# FloatWatch-One.net
KiCad netlist of a schematic drawn in EAGLE
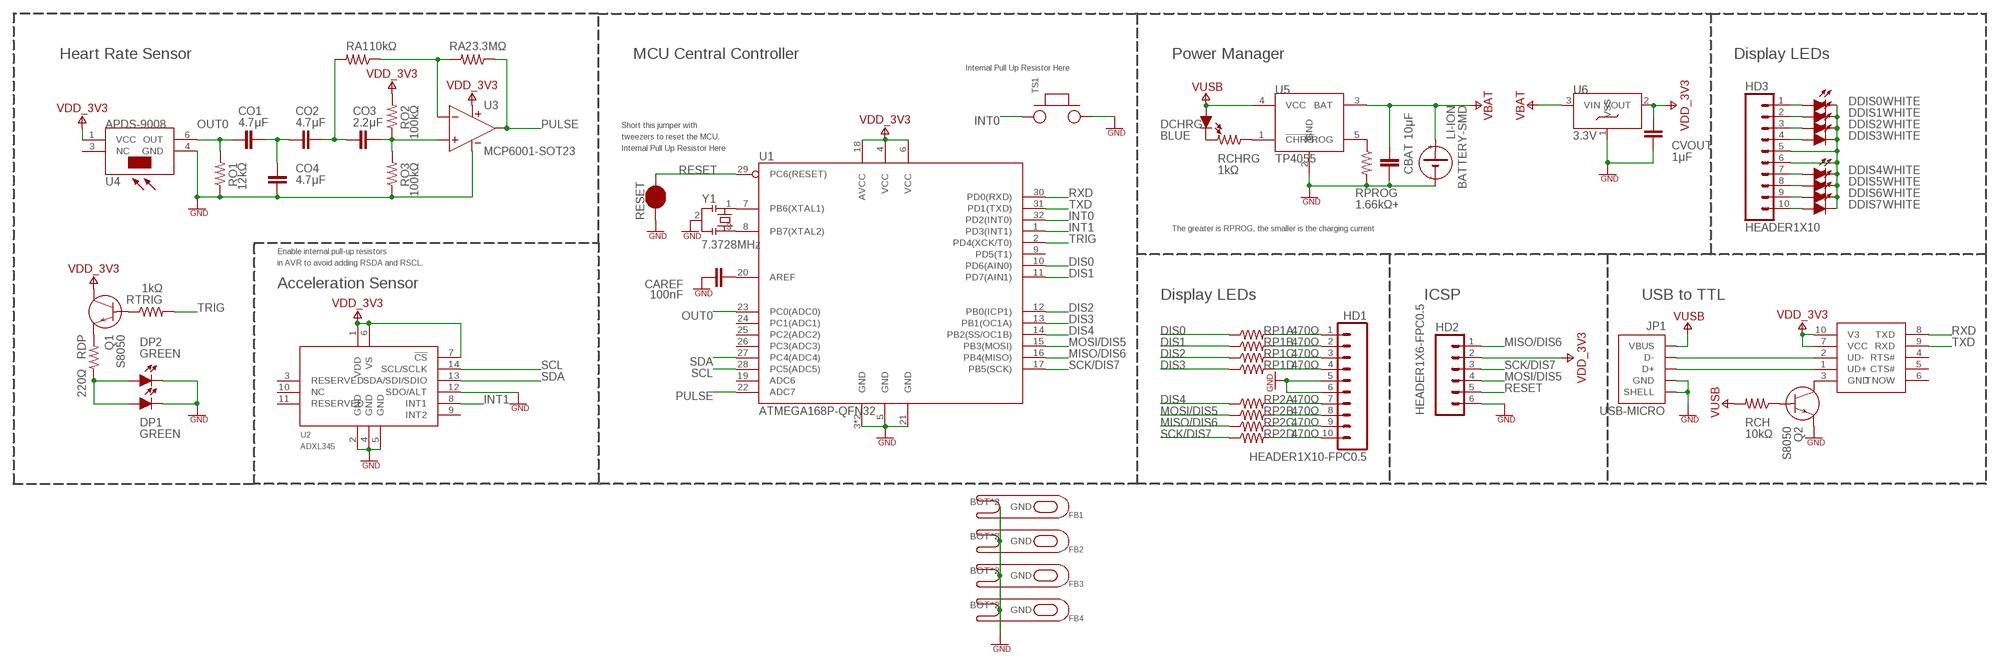
[diagram p0: schematic, sheet 1]

(export (version "E")
  (design (tool "Eeschema 10.0.6"))
  (components
    (comp (ref "CAREF")
      (value "100nF")
      (footprint "eagle-import:SMD0603")
      (libsource (lib "eagle-import") (part "CAP-0603"))
    )
    (comp (ref "CBAT")
      (value "10μF")
      (footprint "eagle-import:SMD0603")
      (libsource (lib "eagle-import") (part "CAP-0603"))
    )
    (comp (ref "CO1")
      (value "4.7μF")
      (footprint "eagle-import:SMD0603")
      (libsource (lib "eagle-import") (part "CAP-0603"))
    )
    (comp (ref "CO2")
      (value "4.7μF")
      (footprint "eagle-import:SMD0603")
      (libsource (lib "eagle-import") (part "CAP-0603"))
    )
    (comp (ref "CO3")
      (value "2.2μF")
      (footprint "eagle-import:SMD0603")
      (libsource (lib "eagle-import") (part "CAP-0603"))
    )
    (comp (ref "CO4")
      (value "4.7μF")
      (footprint "eagle-import:SMD0603")
      (libsource (lib "eagle-import") (part "CAP-0603"))
    )
    (comp (ref "CVOUT")
      (value "1μF")
      (footprint "eagle-import:SMD0603")
      (libsource (lib "eagle-import") (part "CAP-0603"))
    )
    (comp (ref "DCHRG")
      (value "BLUE")
      (footprint "eagle-import:LED-0603")
      (libsource (lib "eagle-import") (part "LED-0603"))
    )
    (comp (ref "DDIS0")
      (value "WHITE")
      (footprint "eagle-import:LED-0603")
      (libsource (lib "eagle-import") (part "LED-0603"))
    )
    (comp (ref "DDIS1")
      (value "WHITE")
      (footprint "eagle-import:LED-0603")
      (libsource (lib "eagle-import") (part "LED-0603"))
    )
    (comp (ref "DDIS2")
      (value "WHITE")
      (footprint "eagle-import:LED-0603")
      (libsource (lib "eagle-import") (part "LED-0603"))
    )
    (comp (ref "DDIS3")
      (value "WHITE")
      (footprint "eagle-import:LED-0603")
      (libsource (lib "eagle-import") (part "LED-0603"))
    )
    (comp (ref "DDIS4")
      (value "WHITE")
      (footprint "eagle-import:LED-0603")
      (libsource (lib "eagle-import") (part "LED-0603"))
    )
    (comp (ref "DDIS5")
      (value "WHITE")
      (footprint "eagle-import:LED-0603")
      (libsource (lib "eagle-import") (part "LED-0603"))
    )
    (comp (ref "DDIS6")
      (value "WHITE")
      (footprint "eagle-import:LED-0603")
      (libsource (lib "eagle-import") (part "LED-0603"))
    )
    (comp (ref "DDIS7")
      (value "WHITE")
      (footprint "eagle-import:LED-0603")
      (libsource (lib "eagle-import") (part "LED-0603"))
    )
    (comp (ref "DP1")
      (value "GREEN")
      (footprint "eagle-import:LED-1206")
      (libsource (lib "eagle-import") (part "LED-1206"))
    )
    (comp (ref "DP2")
      (value "GREEN")
      (footprint "eagle-import:LED-1206")
      (libsource (lib "eagle-import") (part "LED-1206"))
    )
    (comp (ref "FB1")
      (value "BROAD-STICK")
      (footprint "eagle-import:BOARD-STICK")
      (libsource (lib "eagle-import") (part "BROAD-STICK"))
    )
    (comp (ref "FB2")
      (value "BROAD-STICK")
      (footprint "eagle-import:BOARD-STICK")
      (libsource (lib "eagle-import") (part "BROAD-STICK"))
    )
    (comp (ref "FB3")
      (value "BROAD-STICK")
      (footprint "eagle-import:BOARD-STICK")
      (libsource (lib "eagle-import") (part "BROAD-STICK"))
    )
    (comp (ref "FB4")
      (value "BROAD-STICK")
      (footprint "eagle-import:BOARD-STICK")
      (libsource (lib "eagle-import") (part "BROAD-STICK"))
    )
    (comp (ref "HD1")
      (value "HEADER1X10-FPC0.5")
      (footprint "eagle-import:FPC0.5-10")
      (libsource (lib "eagle-import") (part "HEADER1X10-FPC0.5"))
    )
    (comp (ref "HD2")
      (value "HEADER1X6-FPC0.5")
      (footprint "eagle-import:FPC0.5-6")
      (libsource (lib "eagle-import") (part "HEADER1X6-FPC0.5"))
    )
    (comp (ref "HD3")
      (value "HEADER1X10")
      (footprint "eagle-import:FPC0.5-10-SOLDER")
      (libsource (lib "eagle-import") (part "HEADER1X10"))
    )
    (comp (ref "JP1")
      (value "USB-MICRO")
      (footprint "eagle-import:USB-MICRO")
      (libsource (lib "eagle-import") (part "USB-MICRO"))
    )
    (comp (ref "LI-ION")
      (value "BATTERY-SMD")
      (footprint "eagle-import:BAT-SMD")
      (libsource (lib "eagle-import") (part "BATTERY-SMD"))
    )
    (comp (ref "Q1")
      (value "S8050")
      (footprint "eagle-import:SOT23-0")
      (libsource (lib "eagle-import") (part "NPN-0"))
    )
    (comp (ref "Q2")
      (value "S8050")
      (footprint "eagle-import:SOT23-0")
      (libsource (lib "eagle-import") (part "NPN-0"))
    )
    (comp (ref "RA1")
      (value "10kΩ")
      (footprint "eagle-import:SMD0603")
      (libsource (lib "eagle-import") (part "RES-0603"))
    )
    (comp (ref "RA2")
      (value "3.3MΩ")
      (footprint "eagle-import:SMD0603")
      (libsource (lib "eagle-import") (part "RES-0603"))
    )
    (comp (ref "RCH")
      (value "10kΩ")
      (footprint "eagle-import:SMD0603")
      (libsource (lib "eagle-import") (part "RES-0603"))
    )
    (comp (ref "RCHRG")
      (value "1kΩ")
      (footprint "eagle-import:SMD0603")
      (libsource (lib "eagle-import") (part "RES-0603"))
    )
    (comp (ref "RDP")
      (value "220Ω")
      (footprint "eagle-import:SMD0603")
      (libsource (lib "eagle-import") (part "RES-0603"))
    )
    (comp (ref "RESET")
      (value "JUMPER-SMD")
      (footprint "eagle-import:JMPER-SMD")
      (libsource (lib "eagle-import") (part "JUMPER-SMD"))
    )
    (comp (ref "RO1")
      (value "12kΩ")
      (footprint "eagle-import:SMD0603")
      (libsource (lib "eagle-import") (part "RES-0603"))
    )
    (comp (ref "RO2")
      (value "100kΩ")
      (footprint "eagle-import:SMD0603")
      (libsource (lib "eagle-import") (part "RES-0603"))
    )
    (comp (ref "RO3")
      (value "100kΩ")
      (footprint "eagle-import:SMD0603")
      (libsource (lib "eagle-import") (part "RES-0603"))
    )
    (comp (ref "RP1")
      (value "470Ω")
      (footprint "eagle-import:RP0603")
      (libsource (lib "eagle-import") (part "RP-0603"))
    )
    (comp (ref "RP2")
      (value "470Ω")
      (footprint "eagle-import:RP0603")
      (libsource (lib "eagle-import") (part "RP-0603"))
    )
    (comp (ref "RPROG")
      (value "1.66kΩ+")
      (footprint "eagle-import:SMD0603")
      (libsource (lib "eagle-import") (part "RES-0603"))
    )
    (comp (ref "RTRIG")
      (value "1kΩ")
      (footprint "eagle-import:SMD0603")
      (libsource (lib "eagle-import") (part "RES-0603"))
    )
    (comp (ref "TS1")
      (value "TS-P")
      (footprint "eagle-import:TS-3X4P")
      (libsource (lib "eagle-import") (part "TS-P"))
    )
    (comp (ref "U1")
      (value "ATMEGA168P-QFN32")
      (footprint "eagle-import:QFN32")
      (libsource (lib "eagle-import") (part "ATMEGA168P-QFN32"))
    )
    (comp (ref "U2")
      (value "ADXL345")
      (footprint "eagle-import:LGA14")
      (libsource (lib "eagle-import") (part "ADXL345"))
    )
    (comp (ref "U3")
      (value "MCP6001-SOT23")
      (footprint "eagle-import:SOT23-5")
      (libsource (lib "eagle-import") (part "MCP6001-SOT23"))
    )
    (comp (ref "U4")
      (value "APDS-9008")
      (footprint "eagle-import:APDS-9008")
      (libsource (lib "eagle-import") (part "APDS-9008"))
    )
    (comp (ref "U5")
      (value "TP4055")
      (footprint "eagle-import:SOT23-5")
      (libsource (lib "eagle-import") (part "TP4055"))
    )
    (comp (ref "U6")
      (value "3.3V")
      (footprint "eagle-import:SOT23-0")
      (libsource (lib "eagle-import") (part "XC6206-0"))
    )
    (comp (ref "U7")
      (value "CH340E")
      (footprint "eagle-import:MSOP10")
      (libsource (lib "eagle-import") (part "CH340E"))
    )
    (comp (ref "Y1")
      (value "7.3728MHz")
      (footprint "eagle-import:CSTCE")
      (libsource (lib "eagle-import") (part "CSTCE"))
    )
  )
  (nets
    (net (code "1") (name "/DIS0") (class "Default")
      (node (ref "RP1") (pin "1") (pinfunction "1_1") (pintype "passive"))
      (node (ref "U1") (pin "10") (pinfunction "PD6(AIN0)_10") (pintype "bidirectional"))
    )
    (net (code "2") (name "/DIS1") (class "Default")
      (node (ref "RP1") (pin "3") (pinfunction "1_3") (pintype "passive"))
      (node (ref "U1") (pin "11") (pinfunction "PD7(AIN1)_11") (pintype "bidirectional"))
    )
    (net (code "3") (name "/DIS2") (class "Default")
      (node (ref "RP1") (pin "5") (pinfunction "1_5") (pintype "passive"))
      (node (ref "U1") (pin "12") (pinfunction "PB0(ICP1)_12") (pintype "bidirectional"))
    )
    (net (code "4") (name "/DIS3") (class "Default")
      (node (ref "RP1") (pin "7") (pinfunction "1_7") (pintype "passive"))
      (node (ref "U1") (pin "13") (pinfunction "PB1(OC1A)_13") (pintype "bidirectional"))
    )
    (net (code "5") (name "/DIS4") (class "Default")
      (node (ref "RP2") (pin "1") (pinfunction "1_1") (pintype "passive"))
      (node (ref "U1") (pin "14") (pinfunction "PB2(SS/OC1B)_14") (pintype "bidirectional"))
    )
    (net (code "6") (name "/INT0") (class "Default")
      (node (ref "TS1") (pin "1") (pinfunction "1_1") (pintype "bidirectional"))
      (node (ref "U1") (pin "32") (pinfunction "PD2(INT0)_32") (pintype "bidirectional"))
    )
    (net (code "7") (name "/INT1") (class "Default")
      (node (ref "U1") (pin "1") (pinfunction "PD3(INT1)_1") (pintype "bidirectional"))
      (node (ref "U2") (pin "8") (pinfunction "INT1_8") (pintype "bidirectional"))
    )
    (net (code "8") (name "/MISO{slash}DIS6") (class "Default")
      (node (ref "HD2") (pin "1") (pinfunction "1_1") (pintype "passive"))
      (node (ref "RP2") (pin "5") (pinfunction "1_5") (pintype "passive"))
      (node (ref "U1") (pin "16") (pinfunction "PB4(MISO)_16") (pintype "bidirectional"))
    )
    (net (code "9") (name "/MOSI{slash}DIS5") (class "Default")
      (node (ref "HD2") (pin "4") (pinfunction "4_4") (pintype "passive"))
      (node (ref "RP2") (pin "3") (pinfunction "1_3") (pintype "passive"))
      (node (ref "U1") (pin "15") (pinfunction "PB3(MOSI)_15") (pintype "bidirectional"))
    )
    (net (code "10") (name "/OUT0") (class "Default")
      (node (ref "CO1") (pin "2") (pinfunction "2_2") (pintype "passive"))
      (node (ref "RO1") (pin "2") (pinfunction "2_2") (pintype "passive"))
      (node (ref "U1") (pin "23") (pinfunction "PC0(ADC0)_23") (pintype "bidirectional"))
      (node (ref "U4") (pin "6") (pinfunction "OUT_6") (pintype "bidirectional"))
    )
    (net (code "11") (name "/PULSE") (class "Default")
      (node (ref "RA2") (pin "1") (pinfunction "1_1") (pintype "passive"))
      (node (ref "U1") (pin "22") (pinfunction "ADC7_22") (pintype "bidirectional"))
      (node (ref "U3") (pin "1") (pinfunction "OUT_1") (pintype "passive"))
    )
    (net (code "12") (name "/RESET") (class "Default")
      (node (ref "HD2") (pin "5") (pinfunction "5_5") (pintype "passive"))
      (node (ref "RESET") (pin "2") (pinfunction "2_2") (pintype "passive"))
      (node (ref "U1") (pin "29") (pinfunction "PC6(RESET)_29") (pintype "bidirectional"))
    )
    (net (code "13") (name "/RXD") (class "Default")
      (node (ref "U1") (pin "30") (pinfunction "PD0(RXD)_30") (pintype "bidirectional"))
      (node (ref "U7") (pin "8") (pinfunction "TXD_8") (pintype "output"))
    )
    (net (code "14") (name "/SCK{slash}DIS7") (class "Default")
      (node (ref "HD2") (pin "3") (pinfunction "3_3") (pintype "passive"))
      (node (ref "RP2") (pin "7") (pinfunction "1_7") (pintype "passive"))
      (node (ref "U1") (pin "17") (pinfunction "PB5(SCK)_17") (pintype "bidirectional"))
    )
    (net (code "15") (name "/SCL") (class "Default")
      (node (ref "U1") (pin "28") (pinfunction "PC5(ADC5)_28") (pintype "bidirectional"))
      (node (ref "U2") (pin "14") (pinfunction "SCL/SCLK_14") (pintype "bidirectional"))
    )
    (net (code "16") (name "/SDA") (class "Default")
      (node (ref "U1") (pin "27") (pinfunction "PC4(ADC4)_27") (pintype "bidirectional"))
      (node (ref "U2") (pin "13") (pinfunction "SDA/SDI/SDIO_13") (pintype "bidirectional"))
    )
    (net (code "17") (name "/TRIG") (class "Default")
      (node (ref "RTRIG") (pin "2") (pinfunction "2_2") (pintype "passive"))
      (node (ref "U1") (pin "2") (pinfunction "PD4(XCK/T0)_2") (pintype "bidirectional"))
    )
    (net (code "18") (name "/TXD") (class "Default")
      (node (ref "U1") (pin "31") (pinfunction "PD1(TXD)_31") (pintype "bidirectional"))
      (node (ref "U7") (pin "9") (pinfunction "RXD_9") (pintype "input"))
    )
    (net (code "19") (name "GND") (class "Default")
      (node (ref "CAREF") (pin "1") (pinfunction "1_1") (pintype "passive"))
      (node (ref "CBAT") (pin "2") (pinfunction "2_2") (pintype "passive"))
      (node (ref "CO4") (pin "2") (pinfunction "2_2") (pintype "passive"))
      (node (ref "CVOUT") (pin "2") (pinfunction "2_2") (pintype "passive"))
      (node (ref "DP1") (pin "C") (pinfunction "C_C") (pintype "passive"))
      (node (ref "DP2") (pin "C") (pinfunction "C_C") (pintype "passive"))
      (node (ref "FB1") (pin "BOT") (pinfunction "GND_BOT") (pintype "bidirectional"))
      (node (ref "FB1") (pin "TOP") (pinfunction "GND_TOP") (pintype "bidirectional"))
      (node (ref "FB2") (pin "BOT") (pinfunction "GND_BOT") (pintype "bidirectional"))
      (node (ref "FB2") (pin "TOP") (pinfunction "GND_TOP") (pintype "bidirectional"))
      (node (ref "FB3") (pin "BOT") (pinfunction "GND_BOT") (pintype "bidirectional"))
      (node (ref "FB3") (pin "TOP") (pinfunction "GND_TOP") (pintype "bidirectional"))
      (node (ref "FB4") (pin "BOT") (pinfunction "GND_BOT") (pintype "bidirectional"))
      (node (ref "FB4") (pin "TOP") (pinfunction "GND_TOP") (pintype "bidirectional"))
      (node (ref "HD1") (pin "5") (pinfunction "5_5") (pintype "passive"))
      (node (ref "HD1") (pin "6") (pinfunction "6_6") (pintype "passive"))
      (node (ref "HD2") (pin "6") (pinfunction "6_6") (pintype "passive"))
      (node (ref "JP1") (pin "5") (pinfunction "GND_5") (pintype "bidirectional"))
      (node (ref "JP1") (pin "P1") (pinfunction "SHELL_P1") (pintype "bidirectional"))
      (node (ref "JP1") (pin "P2") (pinfunction "SHELL_P2") (pintype "bidirectional"))
      (node (ref "JP1") (pin "P3") (pinfunction "SHELL_P3") (pintype "bidirectional"))
      (node (ref "JP1") (pin "P4") (pinfunction "SHELL_P4") (pintype "bidirectional"))
      (node (ref "LI-ION") (pin "-") (pinfunction "-_-") (pintype "passive"))
      (node (ref "Q2") (pin "2") (pinfunction "E_2") (pintype "input"))
      (node (ref "RESET") (pin "1") (pinfunction "1_1") (pintype "passive"))
      (node (ref "RO1") (pin "1") (pinfunction "1_1") (pintype "passive"))
      (node (ref "RO3") (pin "1") (pinfunction "1_1") (pintype "passive"))
      (node (ref "RPROG") (pin "2") (pinfunction "2_2") (pintype "passive"))
      (node (ref "TS1") (pin "2") (pinfunction "2_2") (pintype "bidirectional"))
      (node (ref "U1") (pin "21") (pinfunction "GND_21") (pintype "bidirectional"))
      (node (ref "U1") (pin "3") (pinfunction "GND_3") (pintype "bidirectional"))
      (node (ref "U1") (pin "5") (pinfunction "GND_5") (pintype "bidirectional"))
      (node (ref "U1") (pin "EP") (pinfunction "GND_EP") (pintype "bidirectional"))
      (node (ref "U2") (pin "12") (pinfunction "SDO/ALT_12") (pintype "bidirectional"))
      (node (ref "U2") (pin "2") (pinfunction "GND_2") (pintype "bidirectional"))
      (node (ref "U2") (pin "4") (pinfunction "GND_4") (pintype "bidirectional"))
      (node (ref "U2") (pin "5") (pinfunction "GND_5") (pintype "bidirectional"))
      (node (ref "U3") (pin "2") (pinfunction "VSS_2") (pintype "passive"))
      (node (ref "U4") (pin "4") (pinfunction "GND_4") (pintype "bidirectional"))
      (node (ref "U5") (pin "2") (pinfunction "GND_2") (pintype "bidirectional"))
      (node (ref "U6") (pin "1") (pinfunction "VSS_1") (pintype "bidirectional"))
      (node (ref "Y1") (pin "2") (pinfunction "2_2") (pintype "passive"))
    )
    (net (code "20") (name "Net-(CO1-Pad1)") (class "Default")
      (node (ref "CO1") (pin "1") (pinfunction "1_1") (pintype "passive"))
      (node (ref "CO2") (pin "2") (pinfunction "2_2") (pintype "passive"))
      (node (ref "CO4") (pin "1") (pinfunction "1_1") (pintype "passive"))
    )
    (net (code "21") (name "Net-(CO2-Pad1)") (class "Default")
      (node (ref "CO2") (pin "1") (pinfunction "1_1") (pintype "passive"))
      (node (ref "CO3") (pin "2") (pinfunction "2_2") (pintype "passive"))
      (node (ref "RA1") (pin "2") (pinfunction "2_2") (pintype "passive"))
    )
    (net (code "22") (name "Net-(DCHRG-PadC)") (class "Default")
      (node (ref "DCHRG") (pin "C") (pinfunction "C_C") (pintype "passive"))
      (node (ref "RCHRG") (pin "2") (pinfunction "2_2") (pintype "passive"))
    )
    (net (code "23") (name "Net-(DDIS0-PadA)") (class "Default")
      (node (ref "DDIS0") (pin "A") (pinfunction "A_A") (pintype "passive"))
      (node (ref "HD3") (pin "1") (pinfunction "1_1") (pintype "passive"))
    )
    (net (code "24") (name "Net-(DDIS0-PadC)") (class "Default")
      (node (ref "DDIS0") (pin "C") (pinfunction "C_C") (pintype "passive"))
      (node (ref "DDIS1") (pin "C") (pinfunction "C_C") (pintype "passive"))
      (node (ref "DDIS2") (pin "C") (pinfunction "C_C") (pintype "passive"))
      (node (ref "DDIS3") (pin "C") (pinfunction "C_C") (pintype "passive"))
      (node (ref "DDIS4") (pin "C") (pinfunction "C_C") (pintype "passive"))
      (node (ref "DDIS5") (pin "C") (pinfunction "C_C") (pintype "passive"))
      (node (ref "DDIS6") (pin "C") (pinfunction "C_C") (pintype "passive"))
      (node (ref "DDIS7") (pin "C") (pinfunction "C_C") (pintype "passive"))
      (node (ref "HD3") (pin "5") (pinfunction "5_5") (pintype "passive"))
      (node (ref "HD3") (pin "6") (pinfunction "6_6") (pintype "passive"))
    )
    (net (code "25") (name "Net-(DDIS1-PadA)") (class "Default")
      (node (ref "DDIS1") (pin "A") (pinfunction "A_A") (pintype "passive"))
      (node (ref "HD3") (pin "2") (pinfunction "2_2") (pintype "passive"))
    )
    (net (code "26") (name "Net-(DDIS2-PadA)") (class "Default")
      (node (ref "DDIS2") (pin "A") (pinfunction "A_A") (pintype "passive"))
      (node (ref "HD3") (pin "3") (pinfunction "3_3") (pintype "passive"))
    )
    (net (code "27") (name "Net-(DDIS3-PadA)") (class "Default")
      (node (ref "DDIS3") (pin "A") (pinfunction "A_A") (pintype "passive"))
      (node (ref "HD3") (pin "4") (pinfunction "4_4") (pintype "passive"))
    )
    (net (code "28") (name "Net-(DDIS4-PadA)") (class "Default")
      (node (ref "DDIS4") (pin "A") (pinfunction "A_A") (pintype "passive"))
      (node (ref "HD3") (pin "7") (pinfunction "7_7") (pintype "passive"))
    )
    (net (code "29") (name "Net-(DDIS5-PadA)") (class "Default")
      (node (ref "DDIS5") (pin "A") (pinfunction "A_A") (pintype "passive"))
      (node (ref "HD3") (pin "8") (pinfunction "8_8") (pintype "passive"))
    )
    (net (code "30") (name "Net-(DDIS6-PadA)") (class "Default")
      (node (ref "DDIS6") (pin "A") (pinfunction "A_A") (pintype "passive"))
      (node (ref "HD3") (pin "9") (pinfunction "9_9") (pintype "passive"))
    )
    (net (code "31") (name "Net-(DDIS7-PadA)") (class "Default")
      (node (ref "DDIS7") (pin "A") (pinfunction "A_A") (pintype "passive"))
      (node (ref "HD3") (pin "10") (pinfunction "10_10") (pintype "passive"))
    )
    (net (code "32") (name "Net-(DP1-PadA)") (class "Default")
      (node (ref "DP1") (pin "A") (pinfunction "A_A") (pintype "passive"))
      (node (ref "DP2") (pin "A") (pinfunction "A_A") (pintype "passive"))
      (node (ref "RDP") (pin "1") (pinfunction "1_1") (pintype "passive"))
    )
    (net (code "33") (name "Net-(HD1-Pad1)") (class "Default")
      (node (ref "HD1") (pin "1") (pinfunction "1_1") (pintype "passive"))
      (node (ref "RP1") (pin "2") (pinfunction "2_2") (pintype "passive"))
    )
    (net (code "34") (name "Net-(HD1-Pad7)") (class "Default")
      (node (ref "HD1") (pin "7") (pinfunction "7_7") (pintype "passive"))
      (node (ref "RP2") (pin "2") (pinfunction "2_2") (pintype "passive"))
    )
    (net (code "35") (name "Net-(JP1-D+)") (class "Default")
      (node (ref "JP1") (pin "3") (pinfunction "D+_3") (pintype "bidirectional"))
      (node (ref "U7") (pin "1") (pinfunction "UD+_1") (pintype "bidirectional"))
    )
    (net (code "36") (name "Net-(JP1-D-)") (class "Default")
      (node (ref "JP1") (pin "2") (pinfunction "D-_2") (pintype "bidirectional"))
      (node (ref "U7") (pin "2") (pinfunction "UD-_2") (pintype "bidirectional"))
    )
    (net (code "37") (name "Net-(Q1-B)") (class "Default")
      (node (ref "Q1") (pin "1") (pinfunction "B_1") (pintype "input"))
      (node (ref "RTRIG") (pin "1") (pinfunction "1_1") (pintype "passive"))
    )
    (net (code "38") (name "Net-(Q1-E)") (class "Default")
      (node (ref "Q1") (pin "2") (pinfunction "E_2") (pintype "input"))
      (node (ref "RDP") (pin "2") (pinfunction "2_2") (pintype "passive"))
    )
    (net (code "39") (name "Net-(Q2-B)") (class "Default")
      (node (ref "Q2") (pin "1") (pinfunction "B_1") (pintype "input"))
      (node (ref "RCH") (pin "1") (pinfunction "1_1") (pintype "passive"))
    )
    (net (code "40") (name "Net-(Q2-C)") (class "Default")
      (node (ref "Q2") (pin "3") (pinfunction "C_3") (pintype "input"))
      (node (ref "U7") (pin "3") (pinfunction "GND_3") (pintype "bidirectional"))
    )
    (net (code "41") (name "Net-(RP1B-2)") (class "Default")
      (node (ref "HD1") (pin "2") (pinfunction "2_2") (pintype "passive"))
      (node (ref "RP1") (pin "4") (pinfunction "2_4") (pintype "passive"))
    )
    (net (code "42") (name "Net-(RP1C-2)") (class "Default")
      (node (ref "HD1") (pin "3") (pinfunction "3_3") (pintype "passive"))
      (node (ref "RP1") (pin "6") (pinfunction "2_6") (pintype "passive"))
    )
    (net (code "43") (name "Net-(RP1D-2)") (class "Default")
      (node (ref "HD1") (pin "4") (pinfunction "4_4") (pintype "passive"))
      (node (ref "RP1") (pin "8") (pinfunction "2_8") (pintype "passive"))
    )
    (net (code "44") (name "Net-(RP2B-2)") (class "Default")
      (node (ref "HD1") (pin "8") (pinfunction "8_8") (pintype "passive"))
      (node (ref "RP2") (pin "4") (pinfunction "2_4") (pintype "passive"))
    )
    (net (code "45") (name "Net-(RP2C-2)") (class "Default")
      (node (ref "HD1") (pin "9") (pinfunction "9_9") (pintype "passive"))
      (node (ref "RP2") (pin "6") (pinfunction "2_6") (pintype "passive"))
    )
    (net (code "46") (name "Net-(RP2D-2)") (class "Default")
      (node (ref "HD1") (pin "10") (pinfunction "10_10") (pintype "passive"))
      (node (ref "RP2") (pin "8") (pinfunction "2_8") (pintype "passive"))
    )
    (net (code "47") (name "Net-(U1-AREF)") (class "Default")
      (node (ref "CAREF") (pin "2") (pinfunction "2_2") (pintype "passive"))
      (node (ref "U1") (pin "20") (pinfunction "AREF_20") (pintype "bidirectional"))
    )
    (net (code "48") (name "Net-(U1-PB6(XTAL1))") (class "Default")
      (node (ref "U1") (pin "7") (pinfunction "PB6(XTAL1)_7") (pintype "bidirectional"))
      (node (ref "Y1") (pin "1") (pinfunction "1_1") (pintype "passive"))
    )
    (net (code "49") (name "Net-(U1-PB7(XTAL2))") (class "Default")
      (node (ref "U1") (pin "8") (pinfunction "PB7(XTAL2)_8") (pintype "bidirectional"))
      (node (ref "Y1") (pin "3") (pinfunction "3_3") (pintype "passive"))
    )
    (net (code "50") (name "Net-(U3-IN+)") (class "Default")
      (node (ref "CO3") (pin "1") (pinfunction "1_1") (pintype "passive"))
      (node (ref "RO2") (pin "1") (pinfunction "1_1") (pintype "passive"))
      (node (ref "RO3") (pin "2") (pinfunction "2_2") (pintype "passive"))
      (node (ref "U3") (pin "3") (pinfunction "IN+_3") (pintype "passive"))
    )
    (net (code "51") (name "Net-(U3-IN-)") (class "Default")
      (node (ref "RA1") (pin "1") (pinfunction "1_1") (pintype "passive"))
      (node (ref "RA2") (pin "2") (pinfunction "2_2") (pintype "passive"))
      (node (ref "U3") (pin "4") (pinfunction "IN-_4") (pintype "passive"))
    )
    (net (code "52") (name "Net-(U5-PROG)") (class "Default")
      (node (ref "RPROG") (pin "1") (pinfunction "1_1") (pintype "passive"))
      (node (ref "U5") (pin "5") (pinfunction "PROG_5") (pintype "bidirectional"))
    )
    (net (code "53") (name "Net-(U5-~{CHRG})") (class "Default")
      (node (ref "RCHRG") (pin "1") (pinfunction "1_1") (pintype "passive"))
      (node (ref "U5") (pin "1") (pinfunction "~{CHRG}_1") (pintype "bidirectional"))
    )
    (net (code "54") (name "VBAT") (class "Default")
      (node (ref "CBAT") (pin "1") (pinfunction "1_1") (pintype "passive"))
      (node (ref "LI-ION") (pin "+") (pinfunction "+_+") (pintype "passive"))
      (node (ref "U5") (pin "3") (pinfunction "BAT_3") (pintype "bidirectional"))
      (node (ref "U6") (pin "3") (pinfunction "VIN_3") (pintype "bidirectional"))
    )
    (net (code "55") (name "VDD_3V3") (class "Default")
      (node (ref "CVOUT") (pin "1") (pinfunction "1_1") (pintype "passive"))
      (node (ref "HD2") (pin "2") (pinfunction "2_2") (pintype "passive"))
      (node (ref "Q1") (pin "3") (pinfunction "C_3") (pintype "input"))
      (node (ref "RO2") (pin "2") (pinfunction "2_2") (pintype "passive"))
      (node (ref "U1") (pin "18") (pinfunction "AVCC_18") (pintype "bidirectional"))
      (node (ref "U1") (pin "4") (pinfunction "VCC_4") (pintype "bidirectional"))
      (node (ref "U1") (pin "6") (pinfunction "VCC_6") (pintype "bidirectional"))
      (node (ref "U2") (pin "1") (pinfunction "VDD_1") (pintype "bidirectional"))
      (node (ref "U2") (pin "6") (pinfunction "VS_6") (pintype "bidirectional"))
      (node (ref "U2") (pin "7") (pinfunction "~{CS}_7") (pintype "bidirectional"))
      (node (ref "U3") (pin "5") (pinfunction "VDD_5") (pintype "passive"))
      (node (ref "U4") (pin "1") (pinfunction "VCC_1") (pintype "bidirectional"))
      (node (ref "U6") (pin "2") (pinfunction "VOUT_2") (pintype "bidirectional"))
      (node (ref "U7") (pin "10") (pinfunction "V3_10") (pintype "bidirectional"))
      (node (ref "U7") (pin "7") (pinfunction "VCC_7") (pintype "bidirectional"))
    )
    (net (code "56") (name "VUSB") (class "Default")
      (node (ref "DCHRG") (pin "A") (pinfunction "A_A") (pintype "passive"))
      (node (ref "JP1") (pin "1") (pinfunction "VBUS_1") (pintype "bidirectional"))
      (node (ref "RCH") (pin "2") (pinfunction "2_2") (pintype "passive"))
      (node (ref "U5") (pin "4") (pinfunction "VCC_4") (pintype "bidirectional"))
    )
    (net (code "57") (name "unconnected-(U1-ADC6-Pad19)") (class "Default")
      (node (ref "U1") (pin "19") (pinfunction "ADC6_19") (pintype "bidirectional"))
    )
    (net (code "58") (name "unconnected-(U1-PC1(ADC1)-Pad24)") (class "Default")
      (node (ref "U1") (pin "24") (pinfunction "PC1(ADC1)_24") (pintype "bidirectional"))
    )
    (net (code "59") (name "unconnected-(U1-PC2(ADC2)-Pad25)") (class "Default")
      (node (ref "U1") (pin "25") (pinfunction "PC2(ADC2)_25") (pintype "bidirectional"))
    )
    (net (code "60") (name "unconnected-(U1-PC3(ADC3)-Pad26)") (class "Default")
      (node (ref "U1") (pin "26") (pinfunction "PC3(ADC3)_26") (pintype "bidirectional"))
    )
    (net (code "61") (name "unconnected-(U1-PD5(T1)-Pad9)") (class "Default")
      (node (ref "U1") (pin "9") (pinfunction "PD5(T1)_9") (pintype "bidirectional"))
    )
    (net (code "62") (name "unconnected-(U2-INT2-Pad9)") (class "Default")
      (node (ref "U2") (pin "9") (pinfunction "INT2_9") (pintype "bidirectional"))
    )
    (net (code "63") (name "unconnected-(U2-NC-Pad10)") (class "Default")
      (node (ref "U2") (pin "10") (pinfunction "NC_10") (pintype "bidirectional"))
    )
    (net (code "64") (name "unconnected-(U2-RESERVED-Pad3)") (class "Default")
      (node (ref "U2") (pin "3") (pinfunction "RESERVED_3") (pintype "bidirectional"))
    )
    (net (code "65") (name "unconnected-(U2-RESERVED-Pad11)") (class "Default")
      (node (ref "U2") (pin "11") (pinfunction "RESERVED_11") (pintype "bidirectional"))
    )
    (net (code "66") (name "unconnected-(U4-NC-Pad3)") (class "Default")
      (node (ref "U4") (pin "3") (pinfunction "NC_3") (pintype "bidirectional"))
    )
    (net (code "67") (name "unconnected-(U7-CTS#-Pad5)") (class "Default")
      (node (ref "U7") (pin "5") (pinfunction "CTS#_5") (pintype "bidirectional"))
    )
    (net (code "68") (name "unconnected-(U7-RTS#-Pad4)") (class "Default")
      (node (ref "U7") (pin "4") (pinfunction "RTS#_4") (pintype "bidirectional"))
    )
    (net (code "69") (name "unconnected-(U7-TNOW-Pad6)") (class "Default")
      (node (ref "U7") (pin "6") (pinfunction "TNOW_6") (pintype "bidirectional"))
    )
  )
)
